# arduino-light-strip.net
KiCad netlist of a schematic drawn in EAGLE
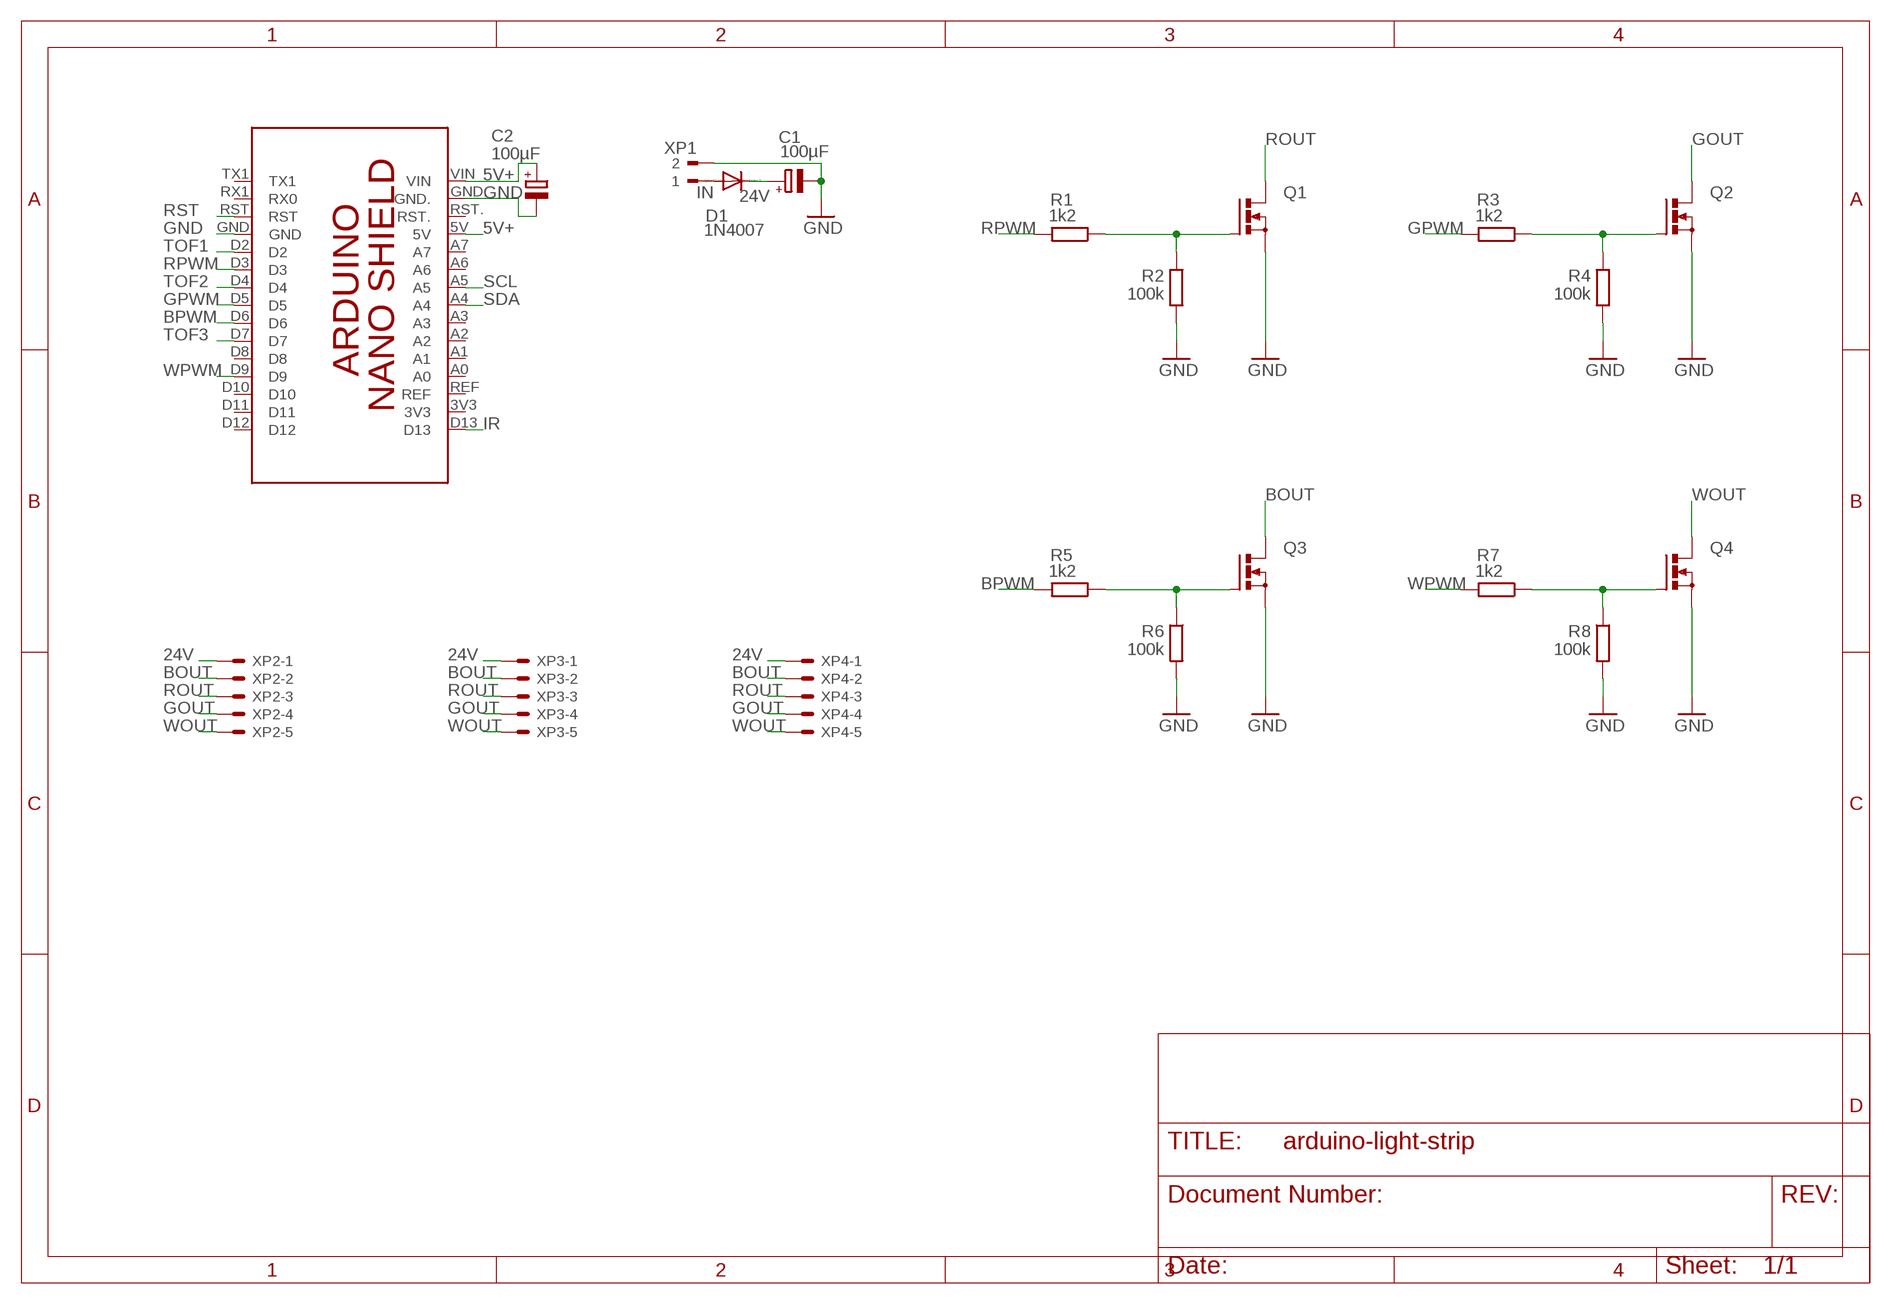
[diagram p0: schematic, sheet 1]

(export (version "E")
  (design (tool "Eeschema 10.0.6"))
  (components
    (comp (ref "C1")
      (value "100µF")
      (footprint "eagle-import:RCL_E5-6")
      (libsource (lib "eagle-import") (part "RCL_CPOL-EUE5-6"))
    )
    (comp (ref "C2")
      (value "100µF")
      (footprint "eagle-import:RCL_E5-6")
      (libsource (lib "eagle-import") (part "RCL_CPOL-EUE5-6"))
    )
    (comp (ref "D1")
      (value "1N4007")
      (footprint "eagle-import:DIODE_F126-10")
      (libsource (lib "eagle-import") (part "DIODE_DIODE-F126-10"))
    )
    (comp (ref "PCB1")
      (value "0_WSH_FAVORITES_ARDUINO_NANO")
      (footprint "eagle-import:0_WSH_FAVORITES_ARDUINO_NANO")
      (libsource (lib "eagle-import") (part "0_WSH_FAVORITES_ARDUINO_NANO"))
    )
    (comp (ref "Q1")
      (value "0_WSH_FAVORITES_BUZ11BV")
      (footprint "eagle-import:0_WSH_FAVORITES_TO220BV")
      (libsource (lib "eagle-import") (part "0_WSH_FAVORITES_BUZ11BV"))
    )
    (comp (ref "Q2")
      (value "0_WSH_FAVORITES_BUZ11BV")
      (footprint "eagle-import:0_WSH_FAVORITES_TO220BV")
      (libsource (lib "eagle-import") (part "0_WSH_FAVORITES_BUZ11BV"))
    )
    (comp (ref "Q3")
      (value "0_WSH_FAVORITES_BUZ11BV")
      (footprint "eagle-import:0_WSH_FAVORITES_TO220BV")
      (libsource (lib "eagle-import") (part "0_WSH_FAVORITES_BUZ11BV"))
    )
    (comp (ref "Q4")
      (value "0_WSH_FAVORITES_BUZ11BV")
      (footprint "eagle-import:0_WSH_FAVORITES_TO220BV")
      (libsource (lib "eagle-import") (part "0_WSH_FAVORITES_BUZ11BV"))
    )
    (comp (ref "R1")
      (value "1k2")
      (footprint "eagle-import:R1206")
      (libsource (lib "eagle-import") (part "R-EU_R1206"))
    )
    (comp (ref "R2")
      (value "100k")
      (footprint "eagle-import:R1206")
      (libsource (lib "eagle-import") (part "R-EU_R1206"))
    )
    (comp (ref "R3")
      (value "1k2")
      (footprint "eagle-import:R1206")
      (libsource (lib "eagle-import") (part "R-EU_R1206"))
    )
    (comp (ref "R4")
      (value "100k")
      (footprint "eagle-import:R1206")
      (libsource (lib "eagle-import") (part "R-EU_R1206"))
    )
    (comp (ref "R5")
      (value "1k2")
      (footprint "eagle-import:R1206")
      (libsource (lib "eagle-import") (part "R-EU_R1206"))
    )
    (comp (ref "R6")
      (value "100k")
      (footprint "eagle-import:R1206")
      (libsource (lib "eagle-import") (part "R-EU_R1206"))
    )
    (comp (ref "R7")
      (value "1k2")
      (footprint "eagle-import:R1206")
      (libsource (lib "eagle-import") (part "R-EU_R1206"))
    )
    (comp (ref "R8")
      (value "100k")
      (footprint "eagle-import:R1206")
      (libsource (lib "eagle-import") (part "R-EU_R1206"))
    )
    (comp (ref "XP1")
      (value "180-3")
      (footprint "eagle-import:CON-WEIDMUELLER-SL35_180-2")
      (libsource (lib "eagle-import") (part "CON-WEIDMUELLER-SL35_180-2"))
    )
    (comp (ref "XP2")
      (value "22-27-2051-05")
      (footprint "eagle-import:6410-05")
      (fields (field (name "MF") "MOLEX"))
      (libsource (lib "eagle-import") (part "22-?-0527-2051"))
    )
    (comp (ref "XP3")
      (value "22-27-2051-05")
      (footprint "eagle-import:6410-05")
      (fields (field (name "MF") "MOLEX"))
      (libsource (lib "eagle-import") (part "22-?-0527-2051"))
    )
    (comp (ref "XP4")
      (value "22-27-2051-05")
      (footprint "eagle-import:6410-05")
      (fields (field (name "MF") "MOLEX"))
      (libsource (lib "eagle-import") (part "22-?-0527-2051"))
    )
  )
  (nets
    (net (code "1") (name "/5V+") (class "Default")
      (node (ref "C2") (pin "+") (pinfunction "+_+") (pintype "passive"))
      (node (ref "PCB1") (pin "5V") (pinfunction "5V_5V") (pintype "bidirectional"))
      (node (ref "PCB1") (pin "VIN") (pinfunction "VIN_VIN") (pintype "bidirectional"))
    )
    (net (code "2") (name "/24V") (class "Default")
      (node (ref "C1") (pin "+") (pinfunction "+_+") (pintype "passive"))
      (node (ref "D1") (pin "C") (pinfunction "C_C") (pintype "passive"))
      (node (ref "XP2") (pin "1") (pinfunction "S_1") (pintype "passive"))
      (node (ref "XP3") (pin "1") (pinfunction "S_1") (pintype "passive"))
      (node (ref "XP4") (pin "1") (pinfunction "S_1") (pintype "passive"))
    )
    (net (code "3") (name "/BOUT") (class "Default")
      (node (ref "Q3") (pin "D") (pinfunction "D_D") (pintype "passive"))
      (node (ref "XP2") (pin "2") (pinfunction "S_2") (pintype "passive"))
      (node (ref "XP3") (pin "2") (pinfunction "S_2") (pintype "passive"))
      (node (ref "XP4") (pin "2") (pinfunction "S_2") (pintype "passive"))
    )
    (net (code "4") (name "/BPWM") (class "Default")
      (node (ref "PCB1") (pin "D6") (pinfunction "D6_D6") (pintype "bidirectional"))
      (node (ref "R5") (pin "2") (pinfunction "2_2") (pintype "passive"))
    )
    (net (code "5") (name "/GOUT") (class "Default")
      (node (ref "Q2") (pin "D") (pinfunction "D_D") (pintype "passive"))
      (node (ref "XP2") (pin "4") (pinfunction "S_4") (pintype "passive"))
      (node (ref "XP3") (pin "4") (pinfunction "S_4") (pintype "passive"))
      (node (ref "XP4") (pin "4") (pinfunction "S_4") (pintype "passive"))
    )
    (net (code "6") (name "/GPWM") (class "Default")
      (node (ref "PCB1") (pin "D5") (pinfunction "D5_D5") (pintype "bidirectional"))
      (node (ref "R3") (pin "2") (pinfunction "2_2") (pintype "passive"))
    )
    (net (code "8") (name "/IR") (class "Default")
      (node (ref "PCB1") (pin "D13") (pinfunction "D13_D13") (pintype "bidirectional"))
    )
    (net (code "9") (name "/ROUT") (class "Default")
      (node (ref "Q1") (pin "D") (pinfunction "D_D") (pintype "passive"))
      (node (ref "XP2") (pin "3") (pinfunction "S_3") (pintype "passive"))
      (node (ref "XP3") (pin "3") (pinfunction "S_3") (pintype "passive"))
      (node (ref "XP4") (pin "3") (pinfunction "S_3") (pintype "passive"))
    )
    (net (code "10") (name "/RPWM") (class "Default")
      (node (ref "PCB1") (pin "D3") (pinfunction "D3_D3") (pintype "bidirectional"))
      (node (ref "R1") (pin "2") (pinfunction "2_2") (pintype "passive"))
    )
    (net (code "11") (name "/RST") (class "Default")
      (node (ref "PCB1") (pin "RST") (pinfunction "RST_RST") (pintype "bidirectional"))
    )
    (net (code "12") (name "/SCL") (class "Default")
      (node (ref "PCB1") (pin "A5") (pinfunction "A5_A5") (pintype "bidirectional"))
    )
    (net (code "13") (name "/SDA") (class "Default")
      (node (ref "PCB1") (pin "A4") (pinfunction "A4_A4") (pintype "bidirectional"))
    )
    (net (code "14") (name "/TOF1") (class "Default")
      (node (ref "PCB1") (pin "D2") (pinfunction "D2_D2") (pintype "bidirectional"))
    )
    (net (code "15") (name "/TOF2") (class "Default")
      (node (ref "PCB1") (pin "D4") (pinfunction "D4_D4") (pintype "bidirectional"))
    )
    (net (code "16") (name "/TOF3") (class "Default")
      (node (ref "PCB1") (pin "D7") (pinfunction "D7_D7") (pintype "bidirectional"))
    )
    (net (code "17") (name "/WOUT") (class "Default")
      (node (ref "Q4") (pin "D") (pinfunction "D_D") (pintype "passive"))
      (node (ref "XP2") (pin "5") (pinfunction "S_5") (pintype "passive"))
      (node (ref "XP3") (pin "5") (pinfunction "S_5") (pintype "passive"))
      (node (ref "XP4") (pin "5") (pinfunction "S_5") (pintype "passive"))
    )
    (net (code "18") (name "/WPWM") (class "Default")
      (node (ref "PCB1") (pin "D9") (pinfunction "D9_D9") (pintype "bidirectional"))
      (node (ref "R7") (pin "2") (pinfunction "2_2") (pintype "passive"))
    )
    (net (code "19") (name "GND") (class "Default")
      (node (ref "C1") (pin "-") (pinfunction "-_-") (pintype "passive"))
      (node (ref "C2") (pin "-") (pinfunction "-_-") (pintype "passive"))
      (node (ref "PCB1") (pin "GND") (pinfunction "GND_GND") (pintype "bidirectional"))
      (node (ref "PCB1") (pin "GND.") (pinfunction "GND._GND.") (pintype "bidirectional"))
      (node (ref "Q1") (pin "S") (pinfunction "S_S") (pintype "passive"))
      (node (ref "Q2") (pin "S") (pinfunction "S_S") (pintype "passive"))
      (node (ref "Q3") (pin "S") (pinfunction "S_S") (pintype "passive"))
      (node (ref "Q4") (pin "S") (pinfunction "S_S") (pintype "passive"))
      (node (ref "R2") (pin "2") (pinfunction "2_2") (pintype "passive"))
      (node (ref "R4") (pin "2") (pinfunction "2_2") (pintype "passive"))
      (node (ref "R6") (pin "2") (pinfunction "2_2") (pintype "passive"))
      (node (ref "R8") (pin "2") (pinfunction "2_2") (pintype "passive"))
      (node (ref "XP1") (pin "2") (pinfunction "2_2") (pintype "passive"))
    )
    (net (code "20") (name "Net-(D1-PadA)") (class "Default")
      (node (ref "D1") (pin "A") (pinfunction "A_A") (pintype "passive"))
      (node (ref "XP1") (pin "1") (pinfunction "1_1") (pintype "passive"))
    )
    (net (code "21") (name "Net-(Q1-PadG)") (class "Default")
      (node (ref "Q1") (pin "G") (pinfunction "G_G") (pintype "passive"))
      (node (ref "R1") (pin "1") (pinfunction "1_1") (pintype "passive"))
      (node (ref "R2") (pin "1") (pinfunction "1_1") (pintype "passive"))
    )
    (net (code "22") (name "Net-(Q2-PadG)") (class "Default")
      (node (ref "Q2") (pin "G") (pinfunction "G_G") (pintype "passive"))
      (node (ref "R3") (pin "1") (pinfunction "1_1") (pintype "passive"))
      (node (ref "R4") (pin "1") (pinfunction "1_1") (pintype "passive"))
    )
    (net (code "23") (name "Net-(Q3-PadG)") (class "Default")
      (node (ref "Q3") (pin "G") (pinfunction "G_G") (pintype "passive"))
      (node (ref "R5") (pin "1") (pinfunction "1_1") (pintype "passive"))
      (node (ref "R6") (pin "1") (pinfunction "1_1") (pintype "passive"))
    )
    (net (code "24") (name "Net-(Q4-PadG)") (class "Default")
      (node (ref "Q4") (pin "G") (pinfunction "G_G") (pintype "passive"))
      (node (ref "R7") (pin "1") (pinfunction "1_1") (pintype "passive"))
      (node (ref "R8") (pin "1") (pinfunction "1_1") (pintype "passive"))
    )
    (net (code "25") (name "unconnected-(PCB1-Pad3V3)") (class "Default")
      (node (ref "PCB1") (pin "3V3") (pinfunction "3V3_3V3") (pintype "bidirectional"))
    )
    (net (code "26") (name "unconnected-(PCB1-PadA0)") (class "Default")
      (node (ref "PCB1") (pin "A0") (pinfunction "A0_A0") (pintype "bidirectional"))
    )
    (net (code "27") (name "unconnected-(PCB1-PadA1)") (class "Default")
      (node (ref "PCB1") (pin "A1") (pinfunction "A1_A1") (pintype "bidirectional"))
    )
    (net (code "28") (name "unconnected-(PCB1-PadA2)") (class "Default")
      (node (ref "PCB1") (pin "A2") (pinfunction "A2_A2") (pintype "bidirectional"))
    )
    (net (code "29") (name "unconnected-(PCB1-PadA3)") (class "Default")
      (node (ref "PCB1") (pin "A3") (pinfunction "A3_A3") (pintype "bidirectional"))
    )
    (net (code "30") (name "unconnected-(PCB1-PadA6)") (class "Default")
      (node (ref "PCB1") (pin "A6") (pinfunction "A6_A6") (pintype "bidirectional"))
    )
    (net (code "31") (name "unconnected-(PCB1-PadA7)") (class "Default")
      (node (ref "PCB1") (pin "A7") (pinfunction "A7_A7") (pintype "bidirectional"))
    )
    (net (code "32") (name "unconnected-(PCB1-PadD8)") (class "Default")
      (node (ref "PCB1") (pin "D8") (pinfunction "D8_D8") (pintype "bidirectional"))
    )
    (net (code "33") (name "unconnected-(PCB1-PadD10)") (class "Default")
      (node (ref "PCB1") (pin "D10") (pinfunction "D10_D10") (pintype "bidirectional"))
    )
    (net (code "34") (name "unconnected-(PCB1-PadD11)") (class "Default")
      (node (ref "PCB1") (pin "D11") (pinfunction "D11_D11") (pintype "bidirectional"))
    )
    (net (code "35") (name "unconnected-(PCB1-PadD12)") (class "Default")
      (node (ref "PCB1") (pin "D12") (pinfunction "D12_D12") (pintype "bidirectional"))
    )
    (net (code "36") (name "unconnected-(PCB1-PadREF)") (class "Default")
      (node (ref "PCB1") (pin "REF") (pinfunction "REF_REF") (pintype "bidirectional"))
    )
    (net (code "37") (name "unconnected-(PCB1-PadRST.)") (class "Default")
      (node (ref "PCB1") (pin "RST.") (pinfunction "RST._RST.") (pintype "bidirectional"))
    )
    (net (code "38") (name "unconnected-(PCB1-PadTX1)") (class "Default")
      (node (ref "PCB1") (pin "TX1") (pinfunction "TX1_TX1") (pintype "bidirectional"))
    )
    (net (code "39") (name "unconnected-(PCB1-RX0-PadRX1)") (class "Default")
      (node (ref "PCB1") (pin "RX1") (pinfunction "RX0_RX1") (pintype "bidirectional"))
    )
  )
)
